# MCU-PINS.net
KiCad netlist of a schematic drawn in Altium Designer
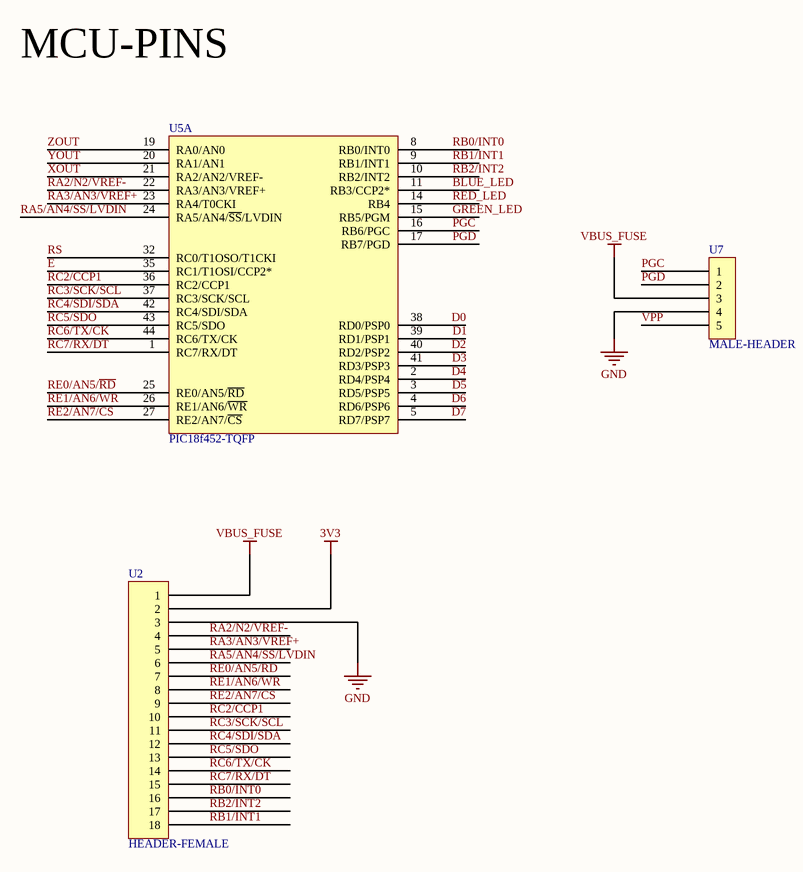
[diagram p0: MCU-PINS.SchDoc]

(export (version "E")
  (design (tool "Eeschema 10.0.6"))
  (components
    (comp (ref "U2")
      (value "HEADER-FEMALE")
      (footprint "HEADER-FEMALE-1-18:PCBComponent_1")
      (libsource (lib "HEADER-FEMALE-1-18") (part "L-KLS1-208B-4.0-1-18-S"))
    )
    (comp (ref "U5")
      (value "PIC18f452-TQFP")
      (footprint "pic16f1937:PCBComponent_1")
      (libsource (lib "dspic30f2023") (part "PIC18f452-TQFP"))
    )
    (comp (ref "U7")
      (value "MALE-HEADER")
      (footprint "MALE-HEADER-5PİNS:PCBComponent_1")
      (libsource (lib "5 header") (part "5-PINS-MALE-HEADER"))
    )
  )
  (nets
    (net (code "1") (name "/BLUE_LED") (class "Default")
      (node (ref "U5") (pin "11") (pinfunction "RB3/CCP2*_11") (pintype "passive"))
    )
    (net (code "2") (name "/D0") (class "Default")
      (node (ref "U5") (pin "38") (pinfunction "RD0/PSP0_38") (pintype "passive"))
    )
    (net (code "3") (name "/D1") (class "Default")
      (node (ref "U5") (pin "39") (pinfunction "RD1/PSP1_39") (pintype "passive"))
    )
    (net (code "4") (name "/D2") (class "Default")
      (node (ref "U5") (pin "40") (pinfunction "RD2/PSP2_40") (pintype "passive"))
    )
    (net (code "5") (name "/D3") (class "Default")
      (node (ref "U5") (pin "41") (pinfunction "RD3/PSP3_41") (pintype "passive"))
    )
    (net (code "6") (name "/D4") (class "Default")
      (node (ref "U5") (pin "2") (pinfunction "RD4/PSP4_2") (pintype "passive"))
    )
    (net (code "7") (name "/D5") (class "Default")
      (node (ref "U5") (pin "3") (pinfunction "RD5/PSP5_3") (pintype "passive"))
    )
    (net (code "8") (name "/D6") (class "Default")
      (node (ref "U5") (pin "4") (pinfunction "RD6/PSP6_4") (pintype "passive"))
    )
    (net (code "9") (name "/D7") (class "Default")
      (node (ref "U5") (pin "5") (pinfunction "RD7/PSP7_5") (pintype "passive"))
    )
    (net (code "10") (name "/E") (class "Default")
      (node (ref "U5") (pin "35") (pinfunction "RC1/T1OSI/CCP2*_35") (pintype "passive"))
    )
    (net (code "11") (name "/GREEN_LED") (class "Default")
      (node (ref "U5") (pin "15") (pinfunction "RB5/PGM_15") (pintype "passive"))
    )
    (net (code "12") (name "/PGC") (class "Default")
      (node (ref "U5") (pin "16") (pinfunction "RB6/PGC_16") (pintype "passive"))
      (node (ref "U7") (pin "1") (pinfunction "1_1") (pintype "passive"))
    )
    (net (code "13") (name "/PGD") (class "Default")
      (node (ref "U5") (pin "17") (pinfunction "RB7/PGD_17") (pintype "passive"))
      (node (ref "U7") (pin "2") (pinfunction "2_2") (pintype "passive"))
    )
    (net (code "14") (name "/RA2{slash}N2{slash}VREF-") (class "Default")
      (node (ref "U2") (pin "4") (pinfunction "4_4") (pintype "passive"))
      (node (ref "U5") (pin "22") (pinfunction "RA3/AN3/VREF+_22") (pintype "passive"))
    )
    (net (code "15") (name "/RA3{slash}AN3{slash}VREF+") (class "Default")
      (node (ref "U2") (pin "5") (pinfunction "5_5") (pintype "passive"))
      (node (ref "U5") (pin "23") (pinfunction "RA4/T0CKI_23") (pintype "passive"))
    )
    (net (code "16") (name "/RA5{slash}AN4{slash}~{SS}{slash}LVDIN") (class "Default")
      (node (ref "U2") (pin "6") (pinfunction "6_6") (pintype "passive"))
      (node (ref "U5") (pin "24") (pinfunction "RA5/AN4/~{SS}/LVDIN_24") (pintype "passive"))
    )
    (net (code "17") (name "/RB0{slash}INT0") (class "Default")
      (node (ref "U2") (pin "16") (pinfunction "16_16") (pintype "passive"))
      (node (ref "U5") (pin "8") (pinfunction "RB0/INT0_8") (pintype "passive"))
    )
    (net (code "18") (name "/RB1{slash}INT1") (class "Default")
      (node (ref "U2") (pin "18") (pinfunction "18_18") (pintype "passive"))
      (node (ref "U5") (pin "9") (pinfunction "RB1/INT1_9") (pintype "passive"))
    )
    (net (code "19") (name "/RB2{slash}INT2") (class "Default")
      (node (ref "U2") (pin "17") (pinfunction "17_17") (pintype "passive"))
      (node (ref "U5") (pin "10") (pinfunction "RB2/INT2_10") (pintype "passive"))
    )
    (net (code "20") (name "/RC2{slash}CCP1") (class "Default")
      (node (ref "U2") (pin "10") (pinfunction "10_10") (pintype "passive"))
      (node (ref "U5") (pin "36") (pinfunction "RC2/CCP1_36") (pintype "passive"))
    )
    (net (code "21") (name "/RC3{slash}SCK{slash}SCL") (class "Default")
      (node (ref "U2") (pin "11") (pinfunction "11_11") (pintype "passive"))
      (node (ref "U5") (pin "37") (pinfunction "RC3/SCK/SCL_37") (pintype "passive"))
    )
    (net (code "22") (name "/RC4{slash}SDI{slash}SDA") (class "Default")
      (node (ref "U2") (pin "12") (pinfunction "12_12") (pintype "passive"))
      (node (ref "U5") (pin "42") (pinfunction "RC4/SDI/SDA_42") (pintype "passive"))
    )
    (net (code "23") (name "/RC5{slash}SDO") (class "Default")
      (node (ref "U2") (pin "13") (pinfunction "13_13") (pintype "passive"))
      (node (ref "U5") (pin "43") (pinfunction "RC5/SDO_43") (pintype "passive"))
    )
    (net (code "24") (name "/RC6{slash}TX{slash}CK") (class "Default")
      (node (ref "U2") (pin "14") (pinfunction "14_14") (pintype "passive"))
      (node (ref "U5") (pin "44") (pinfunction "RC6/TX/CK_44") (pintype "passive"))
    )
    (net (code "25") (name "/RC7{slash}RX{slash}DT") (class "Default")
      (node (ref "U2") (pin "15") (pinfunction "15_15") (pintype "passive"))
      (node (ref "U5") (pin "1") (pinfunction "RC7/RX/DT_1") (pintype "passive"))
    )
    (net (code "26") (name "/RE0{slash}AN5{slash}~{RD}") (class "Default")
      (node (ref "U2") (pin "7") (pinfunction "7_7") (pintype "passive"))
      (node (ref "U5") (pin "25") (pinfunction "RE0/AN5/~{RD}_25") (pintype "passive"))
    )
    (net (code "27") (name "/RE1{slash}AN6{slash}~{WR}") (class "Default")
      (node (ref "U2") (pin "8") (pinfunction "8_8") (pintype "passive"))
      (node (ref "U5") (pin "26") (pinfunction "RE1/AN6/~{WR}_26") (pintype "passive"))
    )
    (net (code "28") (name "/RE2{slash}AN7{slash}~{CS}") (class "Default")
      (node (ref "U2") (pin "9") (pinfunction "9_9") (pintype "passive"))
      (node (ref "U5") (pin "27") (pinfunction "RE2/AN7/~{CS}_27") (pintype "passive"))
    )
    (net (code "29") (name "/RED_LED") (class "Default")
      (node (ref "U5") (pin "14") (pinfunction "RB4_14") (pintype "passive"))
    )
    (net (code "30") (name "/RS") (class "Default")
      (node (ref "U5") (pin "32") (pinfunction "RC0/T1OSO/T1CKI_32") (pintype "passive"))
    )
    (net (code "31") (name "/VPP") (class "Default")
      (node (ref "U7") (pin "5") (pinfunction "5_5") (pintype "passive"))
    )
    (net (code "32") (name "/XOUT") (class "Default")
      (node (ref "U5") (pin "21") (pinfunction "RA2/AN2/VREF-_21") (pintype "passive"))
    )
    (net (code "33") (name "/YOUT") (class "Default")
      (node (ref "U5") (pin "20") (pinfunction "RA1/AN1_20") (pintype "passive"))
    )
    (net (code "34") (name "/ZOUT") (class "Default")
      (node (ref "U5") (pin "19") (pinfunction "RA0/AN0_19") (pintype "passive"))
    )
    (net (code "35") (name "3V3") (class "Default")
      (node (ref "U2") (pin "2") (pinfunction "2_2") (pintype "passive"))
    )
    (net (code "36") (name "GND") (class "Default")
      (node (ref "U2") (pin "3") (pinfunction "3_3") (pintype "passive"))
      (node (ref "U7") (pin "4") (pinfunction "4_4") (pintype "passive"))
    )
    (net (code "37") (name "VBUS_FUSE") (class "Default")
      (node (ref "U2") (pin "1") (pinfunction "1_1") (pintype "passive"))
      (node (ref "U7") (pin "3") (pinfunction "3_3") (pintype "passive"))
    )
  )
)
